# placa_v1.net
KiCad netlist of a schematic drawn in EAGLE
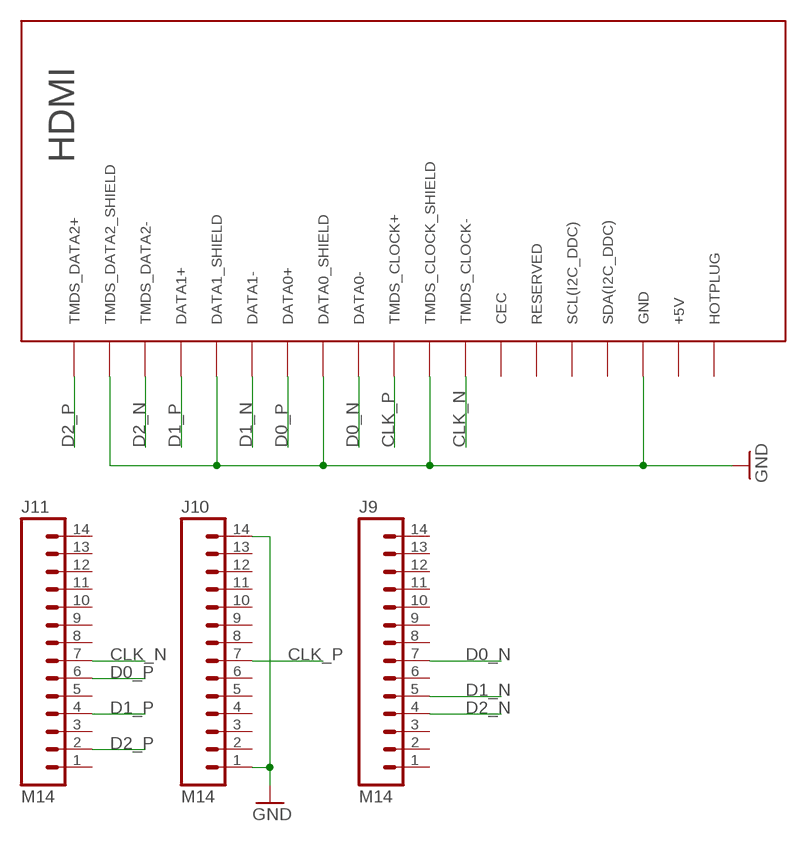
[diagram p0: schematic, sheet 1]

(export (version "E")
  (design (tool "Eeschema 10.0.6"))
  (components
    (comp (ref "J9")
      (value "M14")
      (footprint "eagle-import:1X14")
      (libsource (lib "eagle-import") (part "M14"))
    )
    (comp (ref "J10")
      (value "M14")
      (footprint "eagle-import:1X14")
      (libsource (lib "eagle-import") (part "M14"))
    )
    (comp (ref "J11")
      (value "M14")
      (footprint "eagle-import:1X14")
      (libsource (lib "eagle-import") (part "M14"))
    )
    (comp (ref "U$1")
      (value "HDMI")
      (footprint "eagle-import:HDMI")
      (libsource (lib "eagle-import") (part "HDMI"))
    )
  )
  (nets
    (net (code "1") (name "/CLK_N") (class "Default")
      (node (ref "J11") (pin "7") (pinfunction "7_7") (pintype "passive"))
      (node (ref "U$1") (pin "P$8") (pinfunction "TMDS_CLOCK-_P$8") (pintype "bidirectional"))
    )
    (net (code "2") (name "/CLK_P") (class "Default")
      (node (ref "J10") (pin "7") (pinfunction "7_7") (pintype "passive"))
      (node (ref "U$1") (pin "P$10") (pinfunction "TMDS_CLOCK+_P$10") (pintype "bidirectional"))
    )
    (net (code "3") (name "/D0_N") (class "Default")
      (node (ref "J9") (pin "7") (pinfunction "7_7") (pintype "passive"))
      (node (ref "U$1") (pin "P$11") (pinfunction "DATA0-_P$11") (pintype "bidirectional"))
    )
    (net (code "4") (name "/D0_P") (class "Default")
      (node (ref "J11") (pin "6") (pinfunction "6_6") (pintype "passive"))
      (node (ref "U$1") (pin "P$13") (pinfunction "DATA0+_P$13") (pintype "bidirectional"))
    )
    (net (code "5") (name "/D1_N") (class "Default")
      (node (ref "J9") (pin "5") (pinfunction "5_5") (pintype "passive"))
      (node (ref "U$1") (pin "P$14") (pinfunction "DATA1-_P$14") (pintype "bidirectional"))
    )
    (net (code "6") (name "/D1_P") (class "Default")
      (node (ref "J11") (pin "4") (pinfunction "4_4") (pintype "passive"))
      (node (ref "U$1") (pin "P$16") (pinfunction "DATA1+_P$16") (pintype "bidirectional"))
    )
    (net (code "7") (name "/D2_N") (class "Default")
      (node (ref "J9") (pin "4") (pinfunction "4_4") (pintype "passive"))
      (node (ref "U$1") (pin "P$17") (pinfunction "TMDS_DATA2-_P$17") (pintype "bidirectional"))
    )
    (net (code "8") (name "/D2_P") (class "Default")
      (node (ref "J11") (pin "2") (pinfunction "2_2") (pintype "passive"))
      (node (ref "U$1") (pin "P$19") (pinfunction "TMDS_DATA2+_P$19") (pintype "bidirectional"))
    )
    (net (code "9") (name "GND") (class "Default")
      (node (ref "J10") (pin "1") (pinfunction "1_1") (pintype "passive"))
      (node (ref "J10") (pin "14") (pinfunction "14_14") (pintype "passive"))
      (node (ref "U$1") (pin "P$12") (pinfunction "DATA0_SHIELD_P$12") (pintype "bidirectional"))
      (node (ref "U$1") (pin "P$15") (pinfunction "DATA1_SHIELD_P$15") (pintype "bidirectional"))
      (node (ref "U$1") (pin "P$18") (pinfunction "TMDS_DATA2_SHIELD_P$18") (pintype "bidirectional"))
      (node (ref "U$1") (pin "P$3") (pinfunction "GND_P$3") (pintype "bidirectional"))
      (node (ref "U$1") (pin "P$9") (pinfunction "TMDS_CLOCK_SHIELD_P$9") (pintype "bidirectional"))
    )
    (net (code "10") (name "unconnected-(J9-Pad1)") (class "Default")
      (node (ref "J9") (pin "1") (pinfunction "1_1") (pintype "passive"))
    )
    (net (code "11") (name "unconnected-(J9-Pad2)") (class "Default")
      (node (ref "J9") (pin "2") (pinfunction "2_2") (pintype "passive"))
    )
    (net (code "12") (name "unconnected-(J9-Pad3)") (class "Default")
      (node (ref "J9") (pin "3") (pinfunction "3_3") (pintype "passive"))
    )
    (net (code "13") (name "unconnected-(J9-Pad6)") (class "Default")
      (node (ref "J9") (pin "6") (pinfunction "6_6") (pintype "passive"))
    )
    (net (code "14") (name "unconnected-(J9-Pad8)") (class "Default")
      (node (ref "J9") (pin "8") (pinfunction "8_8") (pintype "passive"))
    )
    (net (code "15") (name "unconnected-(J9-Pad9)") (class "Default")
      (node (ref "J9") (pin "9") (pinfunction "9_9") (pintype "passive"))
    )
    (net (code "16") (name "unconnected-(J9-Pad10)") (class "Default")
      (node (ref "J9") (pin "10") (pinfunction "10_10") (pintype "passive"))
    )
    (net (code "17") (name "unconnected-(J9-Pad11)") (class "Default")
      (node (ref "J9") (pin "11") (pinfunction "11_11") (pintype "passive"))
    )
    (net (code "18") (name "unconnected-(J9-Pad12)") (class "Default")
      (node (ref "J9") (pin "12") (pinfunction "12_12") (pintype "passive"))
    )
    (net (code "19") (name "unconnected-(J9-Pad13)") (class "Default")
      (node (ref "J9") (pin "13") (pinfunction "13_13") (pintype "passive"))
    )
    (net (code "20") (name "unconnected-(J9-Pad14)") (class "Default")
      (node (ref "J9") (pin "14") (pinfunction "14_14") (pintype "passive"))
    )
    (net (code "21") (name "unconnected-(J10-Pad2)") (class "Default")
      (node (ref "J10") (pin "2") (pinfunction "2_2") (pintype "passive"))
    )
    (net (code "22") (name "unconnected-(J10-Pad3)") (class "Default")
      (node (ref "J10") (pin "3") (pinfunction "3_3") (pintype "passive"))
    )
    (net (code "23") (name "unconnected-(J10-Pad4)") (class "Default")
      (node (ref "J10") (pin "4") (pinfunction "4_4") (pintype "passive"))
    )
    (net (code "24") (name "unconnected-(J10-Pad5)") (class "Default")
      (node (ref "J10") (pin "5") (pinfunction "5_5") (pintype "passive"))
    )
    (net (code "25") (name "unconnected-(J10-Pad6)") (class "Default")
      (node (ref "J10") (pin "6") (pinfunction "6_6") (pintype "passive"))
    )
    (net (code "26") (name "unconnected-(J10-Pad8)") (class "Default")
      (node (ref "J10") (pin "8") (pinfunction "8_8") (pintype "passive"))
    )
    (net (code "27") (name "unconnected-(J10-Pad9)") (class "Default")
      (node (ref "J10") (pin "9") (pinfunction "9_9") (pintype "passive"))
    )
    (net (code "28") (name "unconnected-(J10-Pad10)") (class "Default")
      (node (ref "J10") (pin "10") (pinfunction "10_10") (pintype "passive"))
    )
    (net (code "29") (name "unconnected-(J10-Pad11)") (class "Default")
      (node (ref "J10") (pin "11") (pinfunction "11_11") (pintype "passive"))
    )
    (net (code "30") (name "unconnected-(J10-Pad12)") (class "Default")
      (node (ref "J10") (pin "12") (pinfunction "12_12") (pintype "passive"))
    )
    (net (code "31") (name "unconnected-(J10-Pad13)") (class "Default")
      (node (ref "J10") (pin "13") (pinfunction "13_13") (pintype "passive"))
    )
    (net (code "32") (name "unconnected-(J11-Pad1)") (class "Default")
      (node (ref "J11") (pin "1") (pinfunction "1_1") (pintype "passive"))
    )
    (net (code "33") (name "unconnected-(J11-Pad3)") (class "Default")
      (node (ref "J11") (pin "3") (pinfunction "3_3") (pintype "passive"))
    )
    (net (code "34") (name "unconnected-(J11-Pad5)") (class "Default")
      (node (ref "J11") (pin "5") (pinfunction "5_5") (pintype "passive"))
    )
    (net (code "35") (name "unconnected-(J11-Pad8)") (class "Default")
      (node (ref "J11") (pin "8") (pinfunction "8_8") (pintype "passive"))
    )
    (net (code "36") (name "unconnected-(J11-Pad9)") (class "Default")
      (node (ref "J11") (pin "9") (pinfunction "9_9") (pintype "passive"))
    )
    (net (code "37") (name "unconnected-(J11-Pad10)") (class "Default")
      (node (ref "J11") (pin "10") (pinfunction "10_10") (pintype "passive"))
    )
    (net (code "38") (name "unconnected-(J11-Pad11)") (class "Default")
      (node (ref "J11") (pin "11") (pinfunction "11_11") (pintype "passive"))
    )
    (net (code "39") (name "unconnected-(J11-Pad12)") (class "Default")
      (node (ref "J11") (pin "12") (pinfunction "12_12") (pintype "passive"))
    )
    (net (code "40") (name "unconnected-(J11-Pad13)") (class "Default")
      (node (ref "J11") (pin "13") (pinfunction "13_13") (pintype "passive"))
    )
    (net (code "41") (name "unconnected-(J11-Pad14)") (class "Default")
      (node (ref "J11") (pin "14") (pinfunction "14_14") (pintype "passive"))
    )
    (net (code "42") (name "unconnected-(U$1-+5V-PadP$2)") (class "Default")
      (node (ref "U$1") (pin "P$2") (pinfunction "+5V_P$2") (pintype "bidirectional"))
    )
    (net (code "43") (name "unconnected-(U$1-CEC-PadP$7)") (class "Default")
      (node (ref "U$1") (pin "P$7") (pinfunction "CEC_P$7") (pintype "bidirectional"))
    )
    (net (code "44") (name "unconnected-(U$1-HOTPLUG-PadP$1)") (class "Default")
      (node (ref "U$1") (pin "P$1") (pinfunction "HOTPLUG_P$1") (pintype "bidirectional"))
    )
    (net (code "45") (name "unconnected-(U$1-RESERVED-PadP$6)") (class "Default")
      (node (ref "U$1") (pin "P$6") (pinfunction "RESERVED_P$6") (pintype "bidirectional"))
    )
    (net (code "46") (name "unconnected-(U$1-SCL(I2C_DDC)-PadP$5)") (class "Default")
      (node (ref "U$1") (pin "P$5") (pinfunction "SCL(I2C_DDC)_P$5") (pintype "bidirectional"))
    )
    (net (code "47") (name "unconnected-(U$1-SDA(I2C_DDC)-PadP$4)") (class "Default")
      (node (ref "U$1") (pin "P$4") (pinfunction "SDA(I2C_DDC)_P$4") (pintype "bidirectional"))
    )
  )
)
